# untitled.net
KiCad netlist of a schematic drawn in EAGLE
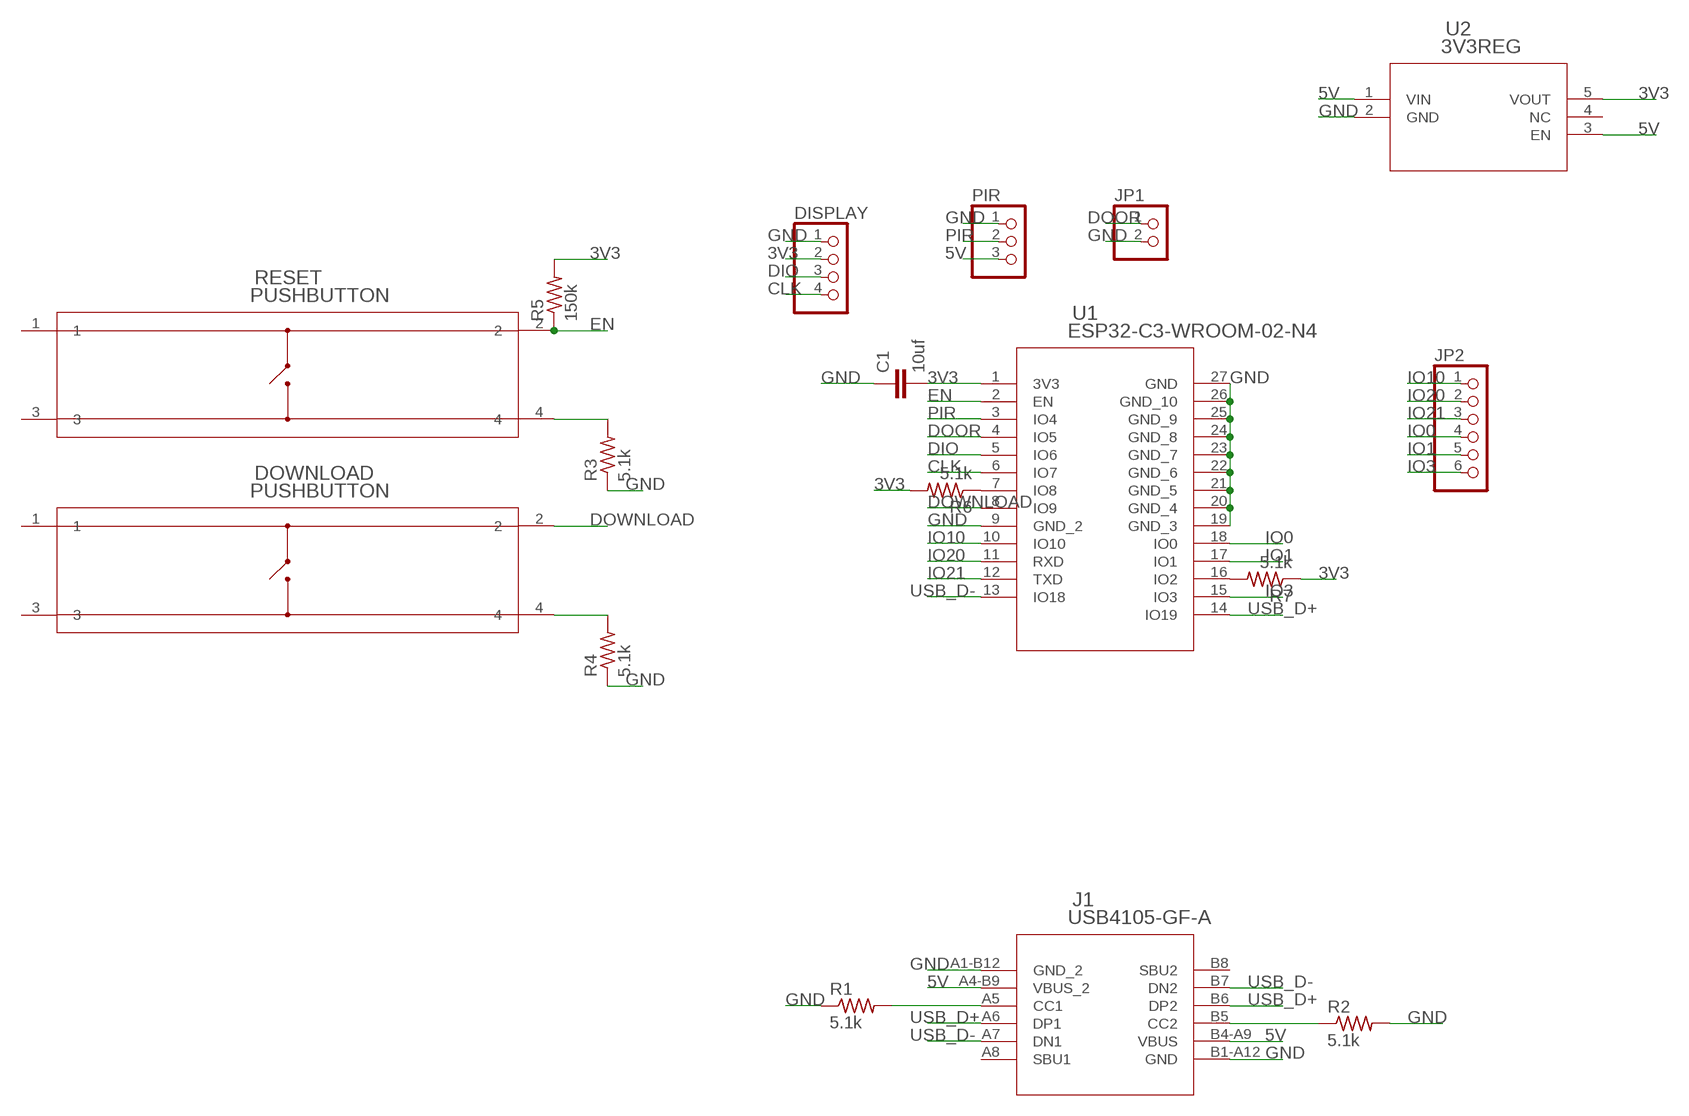
[diagram p0: schematic, sheet 1]

(export (version "E")
  (design (tool "Eeschema 10.0.6"))
  (components
    (comp (ref "C1")
      (value "10uf")
      (footprint "eagle-import:C0805")
      (libsource (lib "eagle-import") (part "C-EUC0805"))
    )
    (comp (ref "DISPLAY")
      (value "PINHD-1X4")
      (footprint "eagle-import:1X04")
      (libsource (lib "eagle-import") (part "PINHD-1X4"))
    )
    (comp (ref "DOWNLOAD")
      (value "PUSHBUTTON")
      (footprint "eagle-import:SW4_PTS815_SJM_250_SMTR_LFS_CN")
      (fields
        (field (name "MANUFACTURER_PART_NUMBER") "PTS815 SJM 250 SMTR LFS")
        (field (name "COPYRIGHT") "Copyright (C) 2023 Ultra Librarian. All rights reserved.")
      )
      (libsource (lib "eagle-import") (part "PUSHBUTTON"))
    )
    (comp (ref "J1")
      (value "USB4105-GF-A")
      (footprint "eagle-import:USB4105_GCT")
      (fields (field (name "COPYRIGHT") "Copyright (C) 2023 Ultra Librarian. All rights reserved."))
      (libsource (lib "eagle-import") (part "USB4105-GF-A"))
    )
    (comp (ref "JP1")
      (value "PINHD-1X2")
      (footprint "eagle-import:1X02")
      (libsource (lib "eagle-import") (part "PINHD-1X2"))
    )
    (comp (ref "JP2")
      (value "PINHD-1X6")
      (footprint "eagle-import:1X06")
      (libsource (lib "eagle-import") (part "PINHD-1X6"))
    )
    (comp (ref "PIR")
      (value "PINHD-1X3")
      (footprint "eagle-import:1X03")
      (libsource (lib "eagle-import") (part "PINHD-1X3"))
    )
    (comp (ref "R1")
      (value "5.1k")
      (footprint "eagle-import:R0603")
      (libsource (lib "eagle-import") (part "R-US_R0603"))
    )
    (comp (ref "R2")
      (value "5.1k")
      (footprint "eagle-import:R0603")
      (libsource (lib "eagle-import") (part "R-US_R0603"))
    )
    (comp (ref "R3")
      (value "5.1k")
      (footprint "eagle-import:R0603")
      (libsource (lib "eagle-import") (part "R-US_R0603"))
    )
    (comp (ref "R4")
      (value "5.1k")
      (footprint "eagle-import:R0603")
      (libsource (lib "eagle-import") (part "R-US_R0603"))
    )
    (comp (ref "R5")
      (value "150k")
      (footprint "eagle-import:R0603")
      (libsource (lib "eagle-import") (part "R-US_R0603"))
    )
    (comp (ref "R6")
      (value "5.1k")
      (footprint "eagle-import:R0603")
      (libsource (lib "eagle-import") (part "R-US_R0603"))
    )
    (comp (ref "R7")
      (value "5.1k")
      (footprint "eagle-import:R0603")
      (libsource (lib "eagle-import") (part "R-US_R0603"))
    )
    (comp (ref "RESET")
      (value "PUSHBUTTON")
      (footprint "eagle-import:SW4_PTS815_SJM_250_SMTR_LFS_CN")
      (fields
        (field (name "MANUFACTURER_PART_NUMBER") "PTS815 SJM 250 SMTR LFS")
        (field (name "COPYRIGHT") "Copyright (C) 2023 Ultra Librarian. All rights reserved.")
      )
      (libsource (lib "eagle-import") (part "PUSHBUTTON"))
    )
    (comp (ref "U1")
      (value "ESP32-C3-WROOM-02-N4")
      (footprint "eagle-import:IC18_ESP32-C3-WROOM-02-N4_EXP")
      (fields (field (name "COPYRIGHT") "Copyright (C) 2023 Ultra Librarian. All rights reserved."))
      (libsource (lib "eagle-import") (part "ESP32-C3-WROOM-02-N4"))
    )
    (comp (ref "U2")
      (value "3V3REG")
      (footprint "eagle-import:SOT_RG1_DIO")
      (fields
        (field (name "MANUFACTURER_PART_NUMBER") "AP2112K-3.3TRG1")
        (field (name "COPYRIGHT") "Copyright (C) 2023 Ultra Librarian. All rights reserved.")
      )
      (libsource (lib "eagle-import") (part "3V3REG"))
    )
  )
  (nets
    (net (code "1") (name "/3V3") (class "Default")
      (node (ref "C1") (pin "2") (pinfunction "2_2") (pintype "passive"))
      (node (ref "DISPLAY") (pin "2") (pinfunction "2_2") (pintype "passive"))
      (node (ref "R5") (pin "2") (pinfunction "2_2") (pintype "passive"))
      (node (ref "R6") (pin "2") (pinfunction "2_2") (pintype "passive"))
      (node (ref "R7") (pin "1") (pinfunction "1_1") (pintype "passive"))
      (node (ref "U1") (pin "1") (pinfunction "3V3_1") (pintype "passive"))
      (node (ref "U2") (pin "5") (pinfunction "VOUT_5") (pintype "passive"))
    )
    (net (code "2") (name "/5V") (class "Default")
      (node (ref "J1") (pin "A4-B9") (pinfunction "VBUS_2_A4-B9") (pintype "power_in"))
      (node (ref "J1") (pin "B4-A9") (pinfunction "VBUS_B4-A9") (pintype "power_in"))
      (node (ref "PIR") (pin "3") (pinfunction "3_3") (pintype "passive"))
      (node (ref "U2") (pin "1") (pinfunction "VIN_1") (pintype "passive"))
      (node (ref "U2") (pin "3") (pinfunction "EN_3") (pintype "passive"))
    )
    (net (code "3") (name "/CLK") (class "Default")
      (node (ref "DISPLAY") (pin "4") (pinfunction "4_4") (pintype "passive"))
      (node (ref "U1") (pin "6") (pinfunction "IO7_6") (pintype "bidirectional"))
    )
    (net (code "4") (name "/DIO") (class "Default")
      (node (ref "DISPLAY") (pin "3") (pinfunction "3_3") (pintype "passive"))
      (node (ref "U1") (pin "5") (pinfunction "IO6_5") (pintype "bidirectional"))
    )
    (net (code "5") (name "/DOOR") (class "Default")
      (node (ref "JP1") (pin "1") (pinfunction "1_1") (pintype "passive"))
      (node (ref "U1") (pin "4") (pinfunction "IO5_4") (pintype "bidirectional"))
    )
    (net (code "6") (name "/DOWNLOAD") (class "Default")
      (node (ref "DOWNLOAD") (pin "2") (pinfunction "2_2") (pintype "passive"))
      (node (ref "U1") (pin "8") (pinfunction "IO9_8") (pintype "bidirectional"))
    )
    (net (code "7") (name "/EN") (class "Default")
      (node (ref "R5") (pin "1") (pinfunction "1_1") (pintype "passive"))
      (node (ref "RESET") (pin "2") (pinfunction "2_2") (pintype "passive"))
      (node (ref "U1") (pin "2") (pinfunction "EN_2") (pintype "passive"))
    )
    (net (code "8") (name "/GND") (class "Default")
      (node (ref "C1") (pin "1") (pinfunction "1_1") (pintype "passive"))
      (node (ref "DISPLAY") (pin "1") (pinfunction "1_1") (pintype "passive"))
      (node (ref "J1") (pin "A1-B12") (pinfunction "GND_2_A1-B12") (pintype "passive"))
      (node (ref "J1") (pin "B1-A12") (pinfunction "GND_B1-A12") (pintype "passive"))
      (node (ref "JP1") (pin "2") (pinfunction "2_2") (pintype "passive"))
      (node (ref "PIR") (pin "1") (pinfunction "1_1") (pintype "passive"))
      (node (ref "R1") (pin "1") (pinfunction "1_1") (pintype "passive"))
      (node (ref "R2") (pin "2") (pinfunction "2_2") (pintype "passive"))
      (node (ref "R3") (pin "1") (pinfunction "1_1") (pintype "passive"))
      (node (ref "R4") (pin "1") (pinfunction "1_1") (pintype "passive"))
      (node (ref "U1") (pin "19") (pinfunction "GND_3_19") (pintype "passive"))
      (node (ref "U1") (pin "20") (pinfunction "GND_4_20") (pintype "passive"))
      (node (ref "U1") (pin "21") (pinfunction "GND_5_21") (pintype "passive"))
      (node (ref "U1") (pin "22") (pinfunction "GND_6_22") (pintype "passive"))
      (node (ref "U1") (pin "23") (pinfunction "GND_7_23") (pintype "passive"))
      (node (ref "U1") (pin "24") (pinfunction "GND_8_24") (pintype "passive"))
      (node (ref "U1") (pin "25") (pinfunction "GND_9_25") (pintype "passive"))
      (node (ref "U1") (pin "26") (pinfunction "GND_10_26") (pintype "passive"))
      (node (ref "U1") (pin "27") (pinfunction "GND_27") (pintype "passive"))
      (node (ref "U1") (pin "9") (pinfunction "GND_2_9") (pintype "passive"))
      (node (ref "U2") (pin "2") (pinfunction "GND_2") (pintype "passive"))
    )
    (net (code "9") (name "/IO0") (class "Default")
      (node (ref "JP2") (pin "4") (pinfunction "4_4") (pintype "passive"))
      (node (ref "U1") (pin "18") (pinfunction "IO0_18") (pintype "bidirectional"))
    )
    (net (code "10") (name "/IO1") (class "Default")
      (node (ref "JP2") (pin "5") (pinfunction "5_5") (pintype "passive"))
      (node (ref "U1") (pin "17") (pinfunction "IO1_17") (pintype "bidirectional"))
    )
    (net (code "11") (name "/IO3") (class "Default")
      (node (ref "JP2") (pin "6") (pinfunction "6_6") (pintype "passive"))
      (node (ref "U1") (pin "15") (pinfunction "IO3_15") (pintype "bidirectional"))
    )
    (net (code "12") (name "/IO10") (class "Default")
      (node (ref "JP2") (pin "1") (pinfunction "1_1") (pintype "passive"))
      (node (ref "U1") (pin "10") (pinfunction "IO10_10") (pintype "bidirectional"))
    )
    (net (code "13") (name "/IO20") (class "Default")
      (node (ref "JP2") (pin "2") (pinfunction "2_2") (pintype "passive"))
      (node (ref "U1") (pin "11") (pinfunction "RXD_11") (pintype "passive"))
    )
    (net (code "14") (name "/IO21") (class "Default")
      (node (ref "JP2") (pin "3") (pinfunction "3_3") (pintype "passive"))
      (node (ref "U1") (pin "12") (pinfunction "TXD_12") (pintype "passive"))
    )
    (net (code "15") (name "/PIR") (class "Default")
      (node (ref "PIR") (pin "2") (pinfunction "2_2") (pintype "passive"))
      (node (ref "U1") (pin "3") (pinfunction "IO4_3") (pintype "bidirectional"))
    )
    (net (code "16") (name "/USB_D+") (class "Default")
      (node (ref "J1") (pin "A6") (pinfunction "DP1_A6") (pintype "bidirectional"))
      (node (ref "J1") (pin "B6") (pinfunction "DP2_B6") (pintype "bidirectional"))
      (node (ref "U1") (pin "14") (pinfunction "IO19_14") (pintype "bidirectional"))
    )
    (net (code "17") (name "/USB_D-") (class "Default")
      (node (ref "J1") (pin "A7") (pinfunction "DN1_A7") (pintype "bidirectional"))
      (node (ref "J1") (pin "B7") (pinfunction "DN2_B7") (pintype "bidirectional"))
      (node (ref "U1") (pin "13") (pinfunction "IO18_13") (pintype "bidirectional"))
    )
    (net (code "18") (name "Net-(DOWNLOAD-Pad4)") (class "Default")
      (node (ref "DOWNLOAD") (pin "4") (pinfunction "4_4") (pintype "passive"))
      (node (ref "R4") (pin "2") (pinfunction "2_2") (pintype "passive"))
    )
    (net (code "19") (name "Net-(J1-CC1)") (class "Default")
      (node (ref "J1") (pin "A5") (pinfunction "CC1_A5") (pintype "bidirectional"))
      (node (ref "R1") (pin "2") (pinfunction "2_2") (pintype "passive"))
    )
    (net (code "20") (name "Net-(J1-CC2)") (class "Default")
      (node (ref "J1") (pin "B5") (pinfunction "CC2_B5") (pintype "bidirectional"))
      (node (ref "R2") (pin "1") (pinfunction "1_1") (pintype "passive"))
    )
    (net (code "21") (name "Net-(R3-Pad2)") (class "Default")
      (node (ref "R3") (pin "2") (pinfunction "2_2") (pintype "passive"))
      (node (ref "RESET") (pin "4") (pinfunction "4_4") (pintype "passive"))
    )
    (net (code "22") (name "Net-(U1-IO2)") (class "Default")
      (node (ref "R7") (pin "2") (pinfunction "2_2") (pintype "passive"))
      (node (ref "U1") (pin "16") (pinfunction "IO2_16") (pintype "bidirectional"))
    )
    (net (code "23") (name "Net-(U1-IO8)") (class "Default")
      (node (ref "R6") (pin "1") (pinfunction "1_1") (pintype "passive"))
      (node (ref "U1") (pin "7") (pinfunction "IO8_7") (pintype "bidirectional"))
    )
    (net (code "24") (name "unconnected-(DOWNLOAD-Pad1)") (class "Default")
      (node (ref "DOWNLOAD") (pin "1") (pinfunction "1_1") (pintype "passive"))
    )
    (net (code "25") (name "unconnected-(DOWNLOAD-Pad3)") (class "Default")
      (node (ref "DOWNLOAD") (pin "3") (pinfunction "3_3") (pintype "passive"))
    )
    (net (code "26") (name "unconnected-(J1-SBU1-PadA8)") (class "Default")
      (node (ref "J1") (pin "A8") (pinfunction "SBU1_A8") (pintype "bidirectional"))
    )
    (net (code "27") (name "unconnected-(J1-SBU2-PadB8)") (class "Default")
      (node (ref "J1") (pin "B8") (pinfunction "SBU2_B8") (pintype "bidirectional"))
    )
    (net (code "28") (name "unconnected-(RESET-Pad1)") (class "Default")
      (node (ref "RESET") (pin "1") (pinfunction "1_1") (pintype "passive"))
    )
    (net (code "29") (name "unconnected-(RESET-Pad3)") (class "Default")
      (node (ref "RESET") (pin "3") (pinfunction "3_3") (pintype "passive"))
    )
    (net (code "30") (name "unconnected-(U2-NC-Pad4)") (class "Default")
      (node (ref "U2") (pin "4") (pinfunction "NC_4") (pintype "passive"))
    )
  )
)
